# GPS_Schematic_Rev2_2.net
KiCad netlist of a schematic drawn in Altium Designer
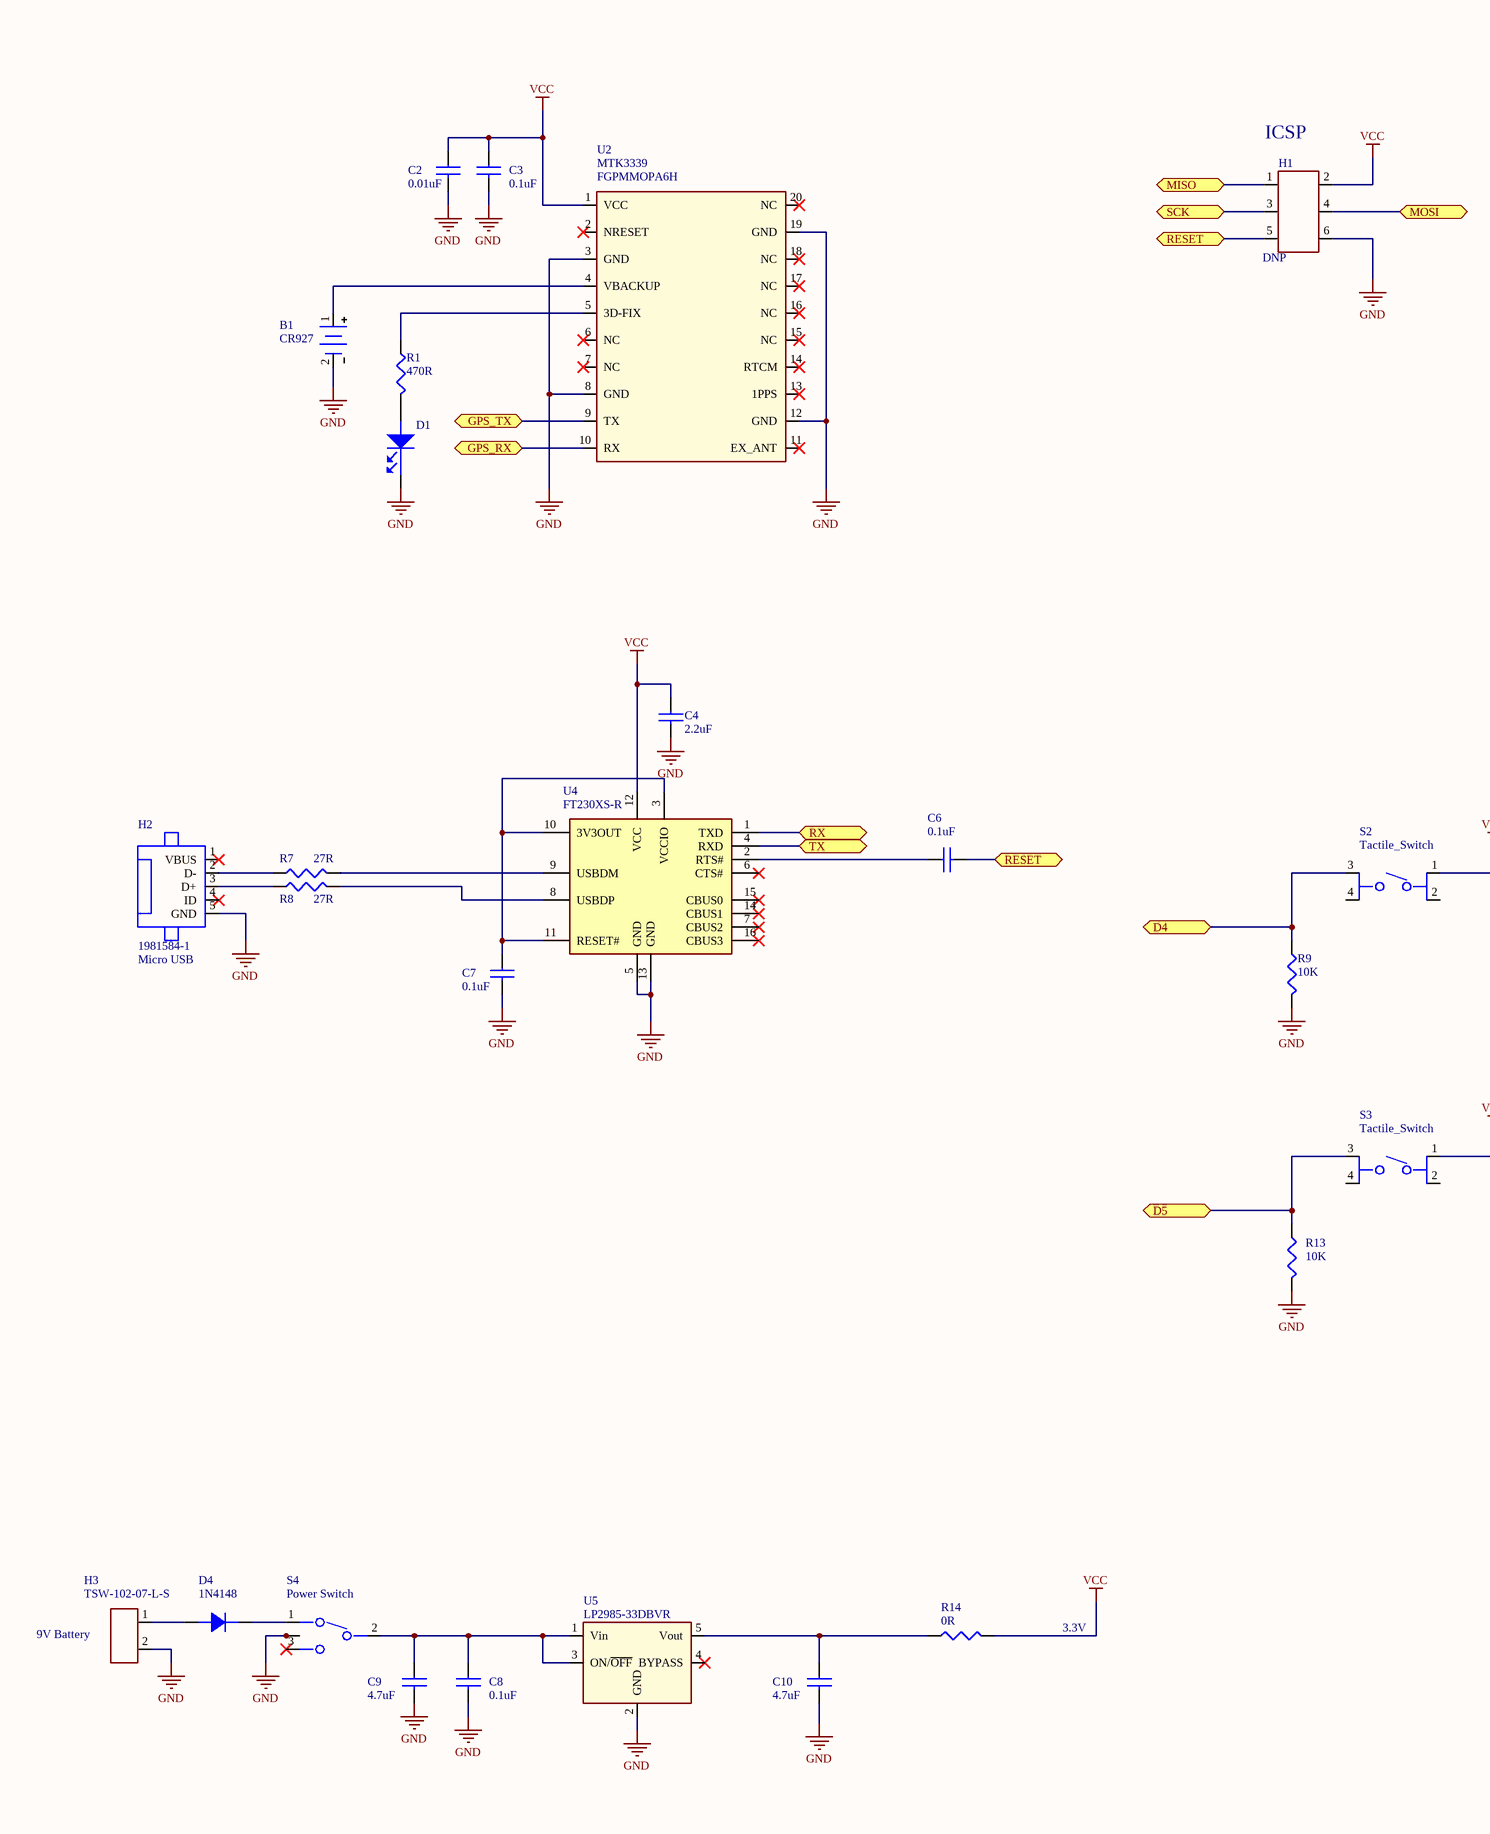
[diagram p0: GPS_Schematic_Rev2.2.SchDoc, left]
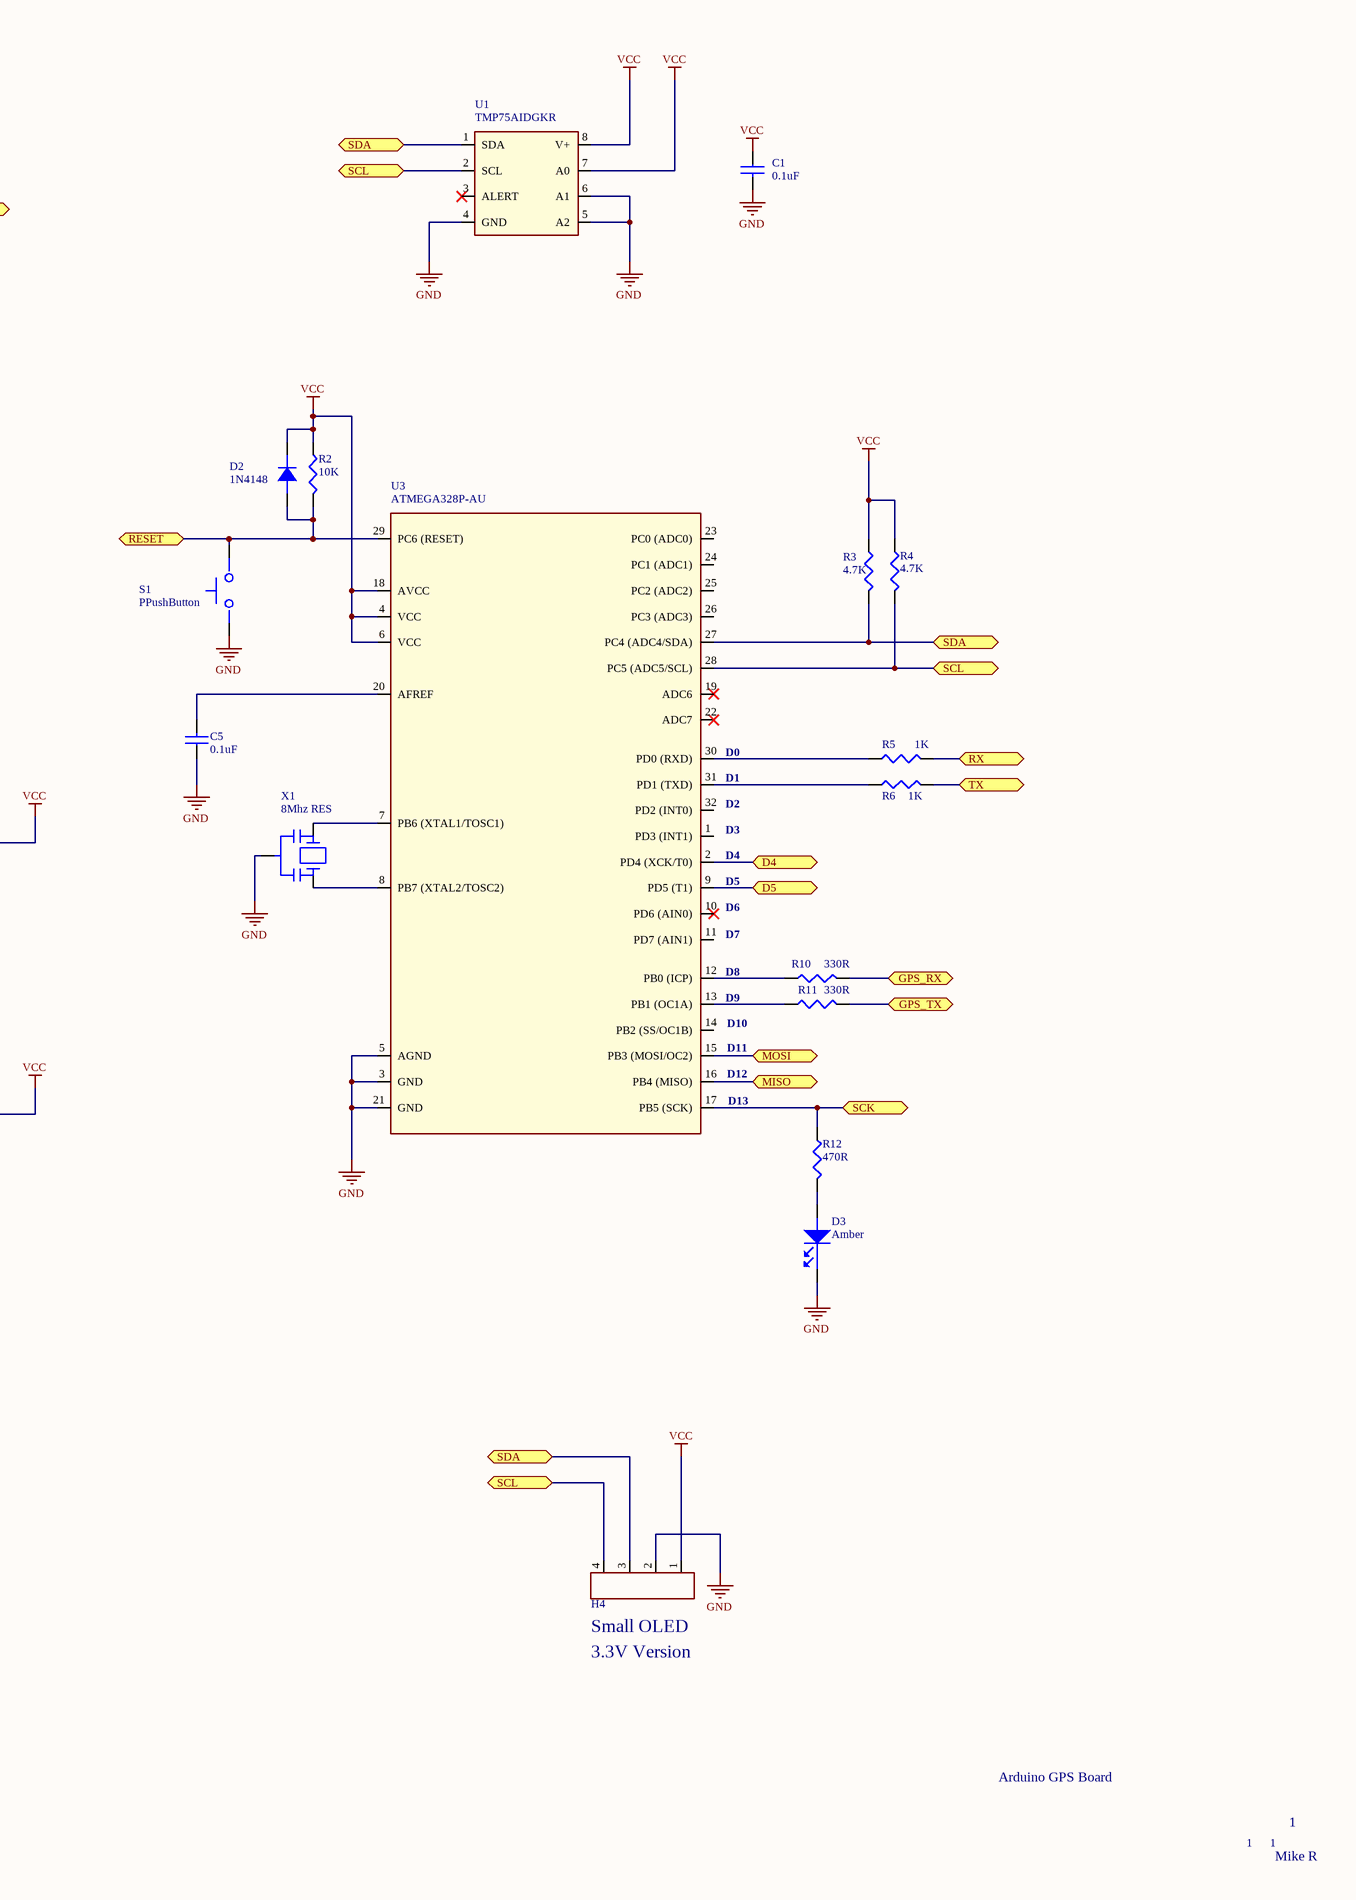
[diagram p1: GPS_Schematic_Rev2.2.SchDoc, right]

(export (version "E")
  (design (tool "Eeschema 10.0.6"))
  (components
    (comp (ref "B1")
      (value "CR927")
      (footprint "CR927 Mount")
      (description "Custom CR927 mount")
      (fields (field (name "PARTNUMBER") "202984"))
      (libsource (lib "Parts_Library") (part "CR927"))
    )
    (comp (ref "C1")
      (value "0.1uF")
      (footprint "CAPC1608X09L")
      (description "CAP CER 0.1uF, 0603")
      (libsource (lib "Parts_Library") (part "CAP_0603"))
    )
    (comp (ref "C2")
      (value "0.01uF")
      (footprint "CAPC1608X09L")
      (description "CAP CER 0.01uF, 0603")
      (libsource (lib "Parts_Library") (part "CAP_0603"))
    )
    (comp (ref "C3")
      (value "0.1uF")
      (footprint "CAPC1608X09L")
      (description "CAP CER 0.1uF, 0603")
      (libsource (lib "Parts_Library") (part "CAP_0603"))
    )
    (comp (ref "C4")
      (value "2.2uF")
      (footprint "CAPC1608X09L")
      (description "2.2uF, 0602")
      (libsource (lib "MAR") (part "CAP_0805"))
    )
    (comp (ref "C5")
      (value "0.1uF")
      (footprint "CAPC1608X09L")
      (description "CAP CER 0.1uF, 0603")
      (libsource (lib "Parts_Library") (part "CAP_0603"))
    )
    (comp (ref "C6")
      (value "0.1uF")
      (footprint "CAPC1608X09L")
      (description "CAP CER 0.1uF, 0603")
      (libsource (lib "Parts_Library") (part "CAP_0603"))
    )
    (comp (ref "C7")
      (value "0.1uF")
      (footprint "CAPC1608X09L")
      (description "CAP CER 0.1uF, 0603")
      (libsource (lib "Parts_Library") (part "CAP_0603"))
    )
    (comp (ref "C8")
      (value "0.1uF")
      (footprint "CAPC1608X09L")
      (description "CAP CER 0.1uF, 0603")
      (libsource (lib "Parts_Library") (part "CAP_0603"))
    )
    (comp (ref "C9")
      (value "4.7uF")
      (footprint "CAPC3216X160L")
      (description "CAP CER 4.7uF, 1206")
      (fields (field (name "Comment") "CAP_1206"))
      (libsource (lib "Parts_Library") (part "CAP_1206"))
    )
    (comp (ref "C10")
      (value "4.7uF")
      (footprint "CAPC3216X160L")
      (description "CAP CER 4.7uF, 1206")
      (fields (field (name "Comment") "CAP_1206"))
      (libsource (lib "Parts_Library") (part "CAP_1206"))
    )
    (comp (ref "D1")
      (value "Green LED")
      (footprint "LED1608X55N-GREEN")
      (description "LED_0603")
      (libsource (lib "Parts_Library") (part "LED_0603"))
    )
    (comp (ref "D2")
      (value "1N4148")
      (footprint "SOD123")
      (description "DIODE SWITCH 100V 0.15A SOD123")
      (fields (field (name "MANUFACTURER") "Micro Commercial") (field (name "PARTNUMBER") "1N4148W-TP"))
      (libsource (lib "MAR") (part "1N4148W-TP"))
    )
    (comp (ref "D3")
      (value "LED_0603")
      (footprint "LED1608X55N-YELLOW")
      (fields (field (name "PARTNUMBER") "Amber"))
      (libsource (lib "MAR") (part "LED_0603"))
    )
    (comp (ref "D4")
      (value "1N4148")
      (footprint "SOD123")
      (description "DIODE SWITCH 100V 0.15A SOD123")
      (fields (field (name "MANUFACTURER") "Micro Commercial") (field (name "PARTNUMBER") "1N4148W-TP"))
      (libsource (lib "MAR") (part "1N4148W-TP"))
    )
    (comp (ref "H1")
      (value "DNP")
      (footprint "HDR3X2")
      (description "CONN HEADER 3X2POS .100\" PADS")
      (libsource (lib "Parts_Library") (part "CON3X2"))
    )
    (comp (ref "H2")
      (value "Micro USB")
      (footprint "1981584-1")
      (description "CONN RCPT MICRO USB TYPE AB")
      (fields (field (name "MANUFACTURER") "TE Connectivity") (field (name "PARTNUMBER") "1981584-1"))
      (libsource (lib "MAR") (part "1981584-1"))
    )
    (comp (ref "H3")
      (value "TSW-102-07-L-S")
      (footprint "HDR1X2")
      (description "CONN HEADER 2POS .100\" SGL GOLD")
      (fields (field (name "MANUFACTURER") "Samtec"))
      (libsource (lib "Parts_Library") (part "TSW-102-07-L-S"))
    )
    (comp (ref "H4")
      (value "TSW-104-07-L-S")
      (footprint "HDR1X4-Empty")
      (description "CONN HEADER 4POS .100\" SGL GOLD")
      (fields (field (name "MANUFACTURER") "Samtec"))
      (libsource (lib "Parts_Library") (part "TSW-104-07-L-S"))
    )
    (comp (ref "R1")
      (value "470R")
      (footprint "RESC1608X06L")
      (description "RES 0603")
      (libsource (lib "MAR") (part "RES_0603"))
    )
    (comp (ref "R2")
      (value "10K")
      (footprint "RESC1608X06L")
      (description "RES 0603")
      (libsource (lib "MAR") (part "RES_0603"))
    )
    (comp (ref "R3")
      (value "4.7K")
      (footprint "RESC1608X06L")
      (description "RES 0603")
      (libsource (lib "MAR") (part "RES_0603"))
    )
    (comp (ref "R4")
      (value "4.7K")
      (footprint "RESC1608X06L")
      (description "RES 0603")
      (libsource (lib "MAR") (part "RES_0603"))
    )
    (comp (ref "R5")
      (value "1K")
      (footprint "RESC1608X06L")
      (description "RES 0603")
      (libsource (lib "MAR") (part "RES_0603"))
    )
    (comp (ref "R6")
      (value "1K")
      (footprint "RESC1608X06L")
      (description "RES 0603")
      (libsource (lib "MAR") (part "RES_0603"))
    )
    (comp (ref "R7")
      (value "27R")
      (footprint "RESC1608X06L")
      (description "RES 0603")
      (libsource (lib "MAR") (part "RES_0603"))
    )
    (comp (ref "R8")
      (value "27R")
      (footprint "RESC1608X06L")
      (description "RES 0603")
      (libsource (lib "MAR") (part "RES_0603"))
    )
    (comp (ref "R9")
      (value "10K")
      (footprint "RESC1608X06L")
      (description "RES 0603")
      (libsource (lib "MAR") (part "RES_0603"))
    )
    (comp (ref "R10")
      (value "330R")
      (footprint "RESC1608X06L")
      (description "RES 0603")
      (libsource (lib "MAR") (part "RES_0603"))
    )
    (comp (ref "R11")
      (value "330R")
      (footprint "RESC1608X06L")
      (description "RES 0603")
      (libsource (lib "MAR") (part "RES_0603"))
    )
    (comp (ref "R12")
      (value "470R")
      (footprint "RESC1608X06L")
      (description "RES 0603")
      (libsource (lib "MAR") (part "RES_0603"))
    )
    (comp (ref "R13")
      (value "10K")
      (footprint "RESC1608X06L")
      (description "RES 0603")
      (libsource (lib "MAR") (part "RES_0603"))
    )
    (comp (ref "R14")
      (value "0R")
      (footprint "RESC1608X06L")
      (description "RES 0603")
      (libsource (lib "MAR") (part "RES_0603"))
    )
    (comp (ref "S1")
      (value "PPushButton")
      (footprint "TL1015AF160QG")
      (description "DX_SWITCH TACTILE")
      (fields (field (name "PARTNUMBER") "122514"))
      (libsource (lib "MAR") (part "DX_MINI_TACT_SWITCH"))
    )
    (comp (ref "S2")
      (value "Tactile_Switch")
      (footprint "FSM6JSMA")
      (description "SWITCH TACTILE SPST-NO 0.05A 12V")
      (fields (field (name "MANUFACTURER") "TE Connectivity") (field (name "PARTNUMBER") "FSM6JSMA"))
      (libsource (lib "Parts_Library") (part "FSM6JSMA"))
    )
    (comp (ref "S3")
      (value "Tactile_Switch")
      (footprint "FSM6JSMA")
      (description "SWITCH TACTILE SPST-NO 0.05A 12V")
      (fields (field (name "MANUFACTURER") "TE Connectivity") (field (name "PARTNUMBER") "FSM6JSMA"))
      (libsource (lib "Parts_Library") (part "FSM6JSMA"))
    )
    (comp (ref "S4")
      (value "~")
      (footprint "SLIDE_SWITCH_DX")
      (description "DX_SWITCH SLIDE SPDT R/A")
      (fields (field (name "PARTNUMBER") "122531"))
      (libsource (lib "MAR") (part "DX_SLIDE_SWITCH"))
    )
    (comp (ref "U1")
      (value "TMP75AIDGKR")
      (footprint "MSOP-8N - NOPAD")
      (description "IC DGTL TEMP SENSOR 2WIRE 8-MSOP")
      (fields (field (name "MANUFACTURER") "Maxim") (field (name "PARTNUMBER") "TMP75AIDGKR"))
      (libsource (lib "MAR") (part "TMP75AIDGKR"))
    )
    (comp (ref "U2")
      (value "MTK3339")
      (footprint "FGPMMOPA6H")
      (description "GPS Chip - FGPMMOPA6H")
      (fields (field (name "MANUFACTURER") "Global Top") (field (name "PARTNUMBER") "FGPMMOPA6H"))
      (libsource (lib "MAR") (part "MTK3339"))
    )
    (comp (ref "U3")
      (value "ATMEGA328P-AU")
      (footprint "TQFP80P700X700-32N")
      (description "MCU AVR 32K FLASH 32TQFP")
      (fields (field (name "MANUFACTURER") "Atmel") (field (name "PARTNUMBER") "ATMEGA328P-AU"))
      (libsource (lib "MAR") (part "ATMEGA328P-AU"))
    )
    (comp (ref "U4")
      (value "FT230XS-R")
      (footprint "SOP65P602X173-16N")
      (description "IC USB SERIAL BASIC UART 16SSOP")
      (fields (field (name "MANUFACTURER") "FTDI") (field (name "PARTNUMBER") "FT230XS-R"))
      (libsource (lib "MAR") (part "FT230XS-R"))
    )
    (comp (ref "U5")
      (value "LP2985-33DBVR")
      (footprint "SOT95P280X144-5N")
      (description "IC REG LDO 3.3V .15A SOT23-5")
      (fields (field (name "MANUFACTURER") "Texas Instruments") (field (name "PARTNUMBER") "LP2985-33DBVR"))
      (libsource (lib "MAR") (part "LP2985-33DBVR"))
    )
    (comp (ref "X1")
      (value "8Mhz RES")
      (footprint "CSTCE")
      (description "CER RESONATOR 8.0MHZ SMD")
      (fields (field (name "PARTNUMBER") "CSTCE8M00G55-R0") (field (name "MANUFACTURER") "Murata"))
      (libsource (lib "Parts_Library") (part "CSTCE8M00G55-R0"))
    )
  )
  (nets
    (net (code "1") (name "/D4") (class "Default")
      (node (ref "R9") (pin "1") (pinfunction "1_1") (pintype "passive"))
      (node (ref "S2") (pin "3") (pintype "passive"))
      (node (ref "U3") (pin "2") (pinfunction "PD4_(XCK/T0)_2") (pintype "passive"))
    )
    (net (code "2") (name "/D5") (class "Default")
      (node (ref "R13") (pin "1") (pinfunction "1_1") (pintype "passive"))
      (node (ref "S3") (pin "3") (pintype "passive"))
      (node (ref "U3") (pin "9") (pinfunction "PD5_(T1)_9") (pintype "passive"))
    )
    (net (code "3") (name "/GPS_RX") (class "Default")
      (node (ref "R10") (pin "2") (pinfunction "2_2") (pintype "passive"))
      (node (ref "U2") (pin "10") (pinfunction "RX_10") (pintype "passive"))
    )
    (net (code "4") (name "/GPS_TX") (class "Default")
      (node (ref "R11") (pin "2") (pinfunction "2_2") (pintype "passive"))
      (node (ref "U2") (pin "9") (pinfunction "TX_9") (pintype "passive"))
    )
    (net (code "5") (name "/MISO") (class "Default")
      (node (ref "H1") (pin "1") (pintype "passive"))
      (node (ref "U3") (pin "16") (pinfunction "PB4_(MISO)_16") (pintype "passive"))
    )
    (net (code "6") (name "/MOSI") (class "Default")
      (node (ref "H1") (pin "4") (pintype "passive"))
      (node (ref "U3") (pin "15") (pinfunction "PB3_(MOSI/OC2)_15") (pintype "passive"))
    )
    (net (code "7") (name "/RESET") (class "Default")
      (node (ref "C6") (pin "2") (pinfunction "2_2") (pintype "passive"))
      (node (ref "D2") (pin "2") (pinfunction "Annode_2") (pintype "passive"))
      (node (ref "H1") (pin "5") (pintype "passive"))
      (node (ref "R2") (pin "2") (pinfunction "2_2") (pintype "passive"))
      (node (ref "S1") (pin "2") (pinfunction "B_2") (pintype "passive"))
      (node (ref "U3") (pin "29") (pinfunction "PC6_(RESET)_29") (pintype "passive"))
    )
    (net (code "8") (name "/RX") (class "Default")
      (node (ref "R5") (pin "2") (pinfunction "2_2") (pintype "passive"))
      (node (ref "U4") (pin "1") (pinfunction "TXD_1") (pintype "passive"))
    )
    (net (code "9") (name "/SCK") (class "Default")
      (node (ref "H1") (pin "3") (pintype "passive"))
      (node (ref "R12") (pin "1") (pinfunction "1_1") (pintype "passive"))
      (node (ref "U3") (pin "17") (pinfunction "PB5_(SCK)_17") (pintype "passive"))
    )
    (net (code "10") (name "/SCL") (class "Default")
      (node (ref "H4") (pin "4") (pintype "passive"))
      (node (ref "R4") (pin "2") (pinfunction "2_2") (pintype "passive"))
      (node (ref "U1") (pin "2") (pinfunction "SCL_2") (pintype "passive"))
      (node (ref "U3") (pin "28") (pinfunction "PC5_(ADC5/SCL)_28") (pintype "passive"))
    )
    (net (code "11") (name "/SDA") (class "Default")
      (node (ref "H4") (pin "3") (pintype "passive"))
      (node (ref "R3") (pin "2") (pinfunction "2_2") (pintype "passive"))
      (node (ref "U1") (pin "1") (pinfunction "SDA_1") (pintype "passive"))
      (node (ref "U3") (pin "27") (pinfunction "PC4_(ADC4/SDA)_27") (pintype "passive"))
    )
    (net (code "12") (name "/TX") (class "Default")
      (node (ref "R6") (pin "2") (pinfunction "2_2") (pintype "passive"))
      (node (ref "U4") (pin "4") (pinfunction "RXD_4") (pintype "passive"))
    )
    (net (code "13") (name "GND") (class "Default")
      (node (ref "B1") (pin "2") (pinfunction "-_2") (pintype "passive"))
      (node (ref "C1") (pin "2") (pinfunction "2_2") (pintype "passive"))
      (node (ref "C10") (pin "2") (pinfunction "2_2") (pintype "passive"))
      (node (ref "C2") (pin "2") (pinfunction "2_2") (pintype "passive"))
      (node (ref "C3") (pin "2") (pinfunction "2_2") (pintype "passive"))
      (node (ref "C4") (pin "2") (pinfunction "2_2") (pintype "passive"))
      (node (ref "C5") (pin "1") (pinfunction "1_1") (pintype "passive"))
      (node (ref "C7") (pin "2") (pinfunction "2_2") (pintype "passive"))
      (node (ref "C8") (pin "2") (pinfunction "2_2") (pintype "passive"))
      (node (ref "C9") (pin "2") (pinfunction "2_2") (pintype "passive"))
      (node (ref "D1") (pin "1") (pinfunction "CATHODE_1") (pintype "passive"))
      (node (ref "D3") (pin "1") (pinfunction "CATHODE_1") (pintype "passive"))
      (node (ref "H1") (pin "6") (pintype "passive"))
      (node (ref "H2") (pin "5") (pinfunction "GND_5") (pintype "power_in"))
      (node (ref "H3") (pin "2") (pintype "passive"))
      (node (ref "H4") (pin "2") (pintype "passive"))
      (node (ref "R13") (pin "2") (pinfunction "2_2") (pintype "passive"))
      (node (ref "R9") (pin "2") (pinfunction "2_2") (pintype "passive"))
      (node (ref "S1") (pin "1") (pinfunction "A_1") (pintype "passive"))
      (node (ref "S4") (pin "4") (pinfunction "GND_4") (pintype "passive"))
      (node (ref "S4") (pin "5") (pinfunction "GND_5") (pintype "passive"))
      (node (ref "U1") (pin "4") (pinfunction "GND_4") (pintype "power_in"))
      (node (ref "U1") (pin "5") (pinfunction "A2_5") (pintype "passive"))
      (node (ref "U1") (pin "6") (pinfunction "A1_6") (pintype "passive"))
      (node (ref "U2") (pin "12") (pinfunction "GND_12") (pintype "power_in"))
      (node (ref "U2") (pin "19") (pinfunction "GND_19") (pintype "power_in"))
      (node (ref "U2") (pin "3") (pinfunction "GND_3") (pintype "power_in"))
      (node (ref "U2") (pin "8") (pinfunction "GND_8") (pintype "power_in"))
      (node (ref "U3") (pin "21") (pinfunction "GND_21") (pintype "power_in"))
      (node (ref "U3") (pin "3") (pinfunction "GND_3") (pintype "power_in"))
      (node (ref "U3") (pin "5") (pinfunction "AGND_5") (pintype "power_in"))
      (node (ref "U4") (pin "13") (pinfunction "GND_13") (pintype "power_in"))
      (node (ref "U4") (pin "5") (pinfunction "GND_5") (pintype "power_in"))
      (node (ref "U5") (pin "2") (pinfunction "GND_2") (pintype "power_in"))
      (node (ref "X1") (pin "2") (pinfunction "2_2") (pintype "passive"))
    )
    (net (code "14") (name "Net-(B1-+)") (class "Default")
      (node (ref "B1") (pin "1") (pinfunction "+_1") (pintype "passive"))
      (node (ref "U2") (pin "4") (pinfunction "VBACKUP_4") (pintype "passive"))
    )
    (net (code "15") (name "Net-(D1-ANODE)") (class "Default")
      (node (ref "D1") (pin "2") (pinfunction "ANODE_2") (pintype "passive"))
      (node (ref "R1") (pin "2") (pinfunction "2_2") (pintype "passive"))
    )
    (net (code "16") (name "Net-(D3-ANODE)") (class "Default")
      (node (ref "D3") (pin "2") (pinfunction "ANODE_2") (pintype "passive"))
      (node (ref "R12") (pin "2") (pinfunction "2_2") (pintype "passive"))
    )
    (net (code "17") (name "Net-(D4-Annode)") (class "Default")
      (node (ref "D4") (pin "2") (pinfunction "Annode_2") (pintype "passive"))
      (node (ref "H3") (pin "1") (pintype "passive"))
    )
    (net (code "18") (name "Net-(D4-Cathode)") (class "Default")
      (node (ref "D4") (pin "1") (pinfunction "Cathode_1") (pintype "passive"))
      (node (ref "S4") (pin "1") (pinfunction "A_1") (pintype "passive"))
    )
    (net (code "19") (name "Net-(H2-D+)") (class "Default")
      (node (ref "H2") (pin "3") (pinfunction "D+_3") (pintype "passive"))
      (node (ref "R8") (pin "1") (pinfunction "1_1") (pintype "passive"))
    )
    (net (code "20") (name "Net-(H2-D-)") (class "Default")
      (node (ref "H2") (pin "2") (pinfunction "D-_2") (pintype "passive"))
      (node (ref "R7") (pin "1") (pinfunction "1_1") (pintype "passive"))
    )
    (net (code "21") (name "Net-(S4-Middle)") (class "Default")
      (node (ref "C8") (pin "1") (pinfunction "1_1") (pintype "passive"))
      (node (ref "C9") (pin "1") (pinfunction "1_1") (pintype "passive"))
      (node (ref "S4") (pin "2") (pinfunction "Middle_2") (pintype "passive"))
      (node (ref "U5") (pin "1") (pinfunction "Vin_1") (pintype "passive"))
      (node (ref "U5") (pin "3") (pinfunction "ON/~{OFF}_3") (pintype "passive"))
    )
    (net (code "22") (name "Net-(U2-3D-FIX)") (class "Default")
      (node (ref "R1") (pin "1") (pinfunction "1_1") (pintype "passive"))
      (node (ref "U2") (pin "5") (pinfunction "3D-FIX_5") (pintype "passive"))
    )
    (net (code "23") (name "Net-(U3-AFREF)") (class "Default")
      (node (ref "C5") (pin "2") (pinfunction "2_2") (pintype "passive"))
      (node (ref "U3") (pin "20") (pinfunction "AFREF_20") (pintype "passive"))
    )
    (net (code "24") (name "Net-(U3-PB0_(ICP))") (class "Default")
      (node (ref "R10") (pin "1") (pinfunction "1_1") (pintype "passive"))
      (node (ref "U3") (pin "12") (pinfunction "PB0_(ICP)_12") (pintype "passive"))
    )
    (net (code "25") (name "Net-(U3-PB1_(OC1A))") (class "Default")
      (node (ref "R11") (pin "1") (pinfunction "1_1") (pintype "passive"))
      (node (ref "U3") (pin "13") (pinfunction "PB1_(OC1A)_13") (pintype "passive"))
    )
    (net (code "26") (name "Net-(U3-PB6_(XTAL1{slash}TOSC1))") (class "Default")
      (node (ref "U3") (pin "7") (pinfunction "PB6_(XTAL1/TOSC1)_7") (pintype "passive"))
      (node (ref "X1") (pin "1") (pinfunction "1_1") (pintype "passive"))
    )
    (net (code "27") (name "Net-(U3-PB7_(XTAL2{slash}TOSC2))") (class "Default")
      (node (ref "U3") (pin "8") (pinfunction "PB7_(XTAL2/TOSC2)_8") (pintype "passive"))
      (node (ref "X1") (pin "3") (pinfunction "3_3") (pintype "passive"))
    )
    (net (code "28") (name "Net-(U3-PD0_(RXD))") (class "Default")
      (node (ref "R5") (pin "1") (pinfunction "1_1") (pintype "passive"))
      (node (ref "U3") (pin "30") (pinfunction "PD0_(RXD)_30") (pintype "passive"))
    )
    (net (code "29") (name "Net-(U3-PD1_(TXD))") (class "Default")
      (node (ref "R6") (pin "1") (pinfunction "1_1") (pintype "passive"))
      (node (ref "U3") (pin "31") (pinfunction "PD1_(TXD)_31") (pintype "passive"))
    )
    (net (code "30") (name "Net-(U4-3V3OUT)") (class "Default")
      (node (ref "C7") (pin "1") (pinfunction "1_1") (pintype "passive"))
      (node (ref "U4") (pin "10") (pinfunction "3V3OUT_10") (pintype "passive"))
      (node (ref "U4") (pin "11") (pinfunction "RESET#_11") (pintype "passive"))
      (node (ref "U4") (pin "3") (pinfunction "VCCIO_3") (pintype "passive"))
    )
    (net (code "31") (name "Net-(U4-RTS#)") (class "Default")
      (node (ref "C6") (pin "1") (pinfunction "1_1") (pintype "passive"))
      (node (ref "U4") (pin "2") (pinfunction "RTS#_2") (pintype "passive"))
    )
    (net (code "32") (name "Net-(U4-USBDM)") (class "Default")
      (node (ref "R7") (pin "2") (pinfunction "2_2") (pintype "passive"))
      (node (ref "U4") (pin "9") (pinfunction "USBDM_9") (pintype "passive"))
    )
    (net (code "33") (name "Net-(U4-USBDP)") (class "Default")
      (node (ref "R8") (pin "2") (pinfunction "2_2") (pintype "passive"))
      (node (ref "U4") (pin "8") (pinfunction "USBDP_8") (pintype "passive"))
    )
    (net (code "34") (name "Net-(U5-Vout)") (class "Default")
      (node (ref "C10") (pin "1") (pinfunction "1_1") (pintype "passive"))
      (node (ref "R14") (pin "1") (pinfunction "1_1") (pintype "passive"))
      (node (ref "U5") (pin "5") (pinfunction "Vout_5") (pintype "passive"))
    )
    (net (code "35") (name "VCC") (class "Default")
      (node (ref "C1") (pin "1") (pinfunction "1_1") (pintype "passive"))
      (node (ref "C2") (pin "1") (pinfunction "1_1") (pintype "passive"))
      (node (ref "C3") (pin "1") (pinfunction "1_1") (pintype "passive"))
      (node (ref "C4") (pin "1") (pinfunction "1_1") (pintype "passive"))
      (node (ref "D2") (pin "1") (pinfunction "Cathode_1") (pintype "passive"))
      (node (ref "H1") (pin "2") (pintype "passive"))
      (node (ref "H4") (pin "1") (pintype "passive"))
      (node (ref "R14") (pin "2") (pinfunction "2_2") (pintype "passive"))
      (node (ref "R2") (pin "1") (pinfunction "1_1") (pintype "passive"))
      (node (ref "R3") (pin "1") (pinfunction "1_1") (pintype "passive"))
      (node (ref "R4") (pin "1") (pinfunction "1_1") (pintype "passive"))
      (node (ref "S2") (pin "1") (pintype "passive"))
      (node (ref "S3") (pin "1") (pintype "passive"))
      (node (ref "U1") (pin "7") (pinfunction "A0_7") (pintype "passive"))
      (node (ref "U1") (pin "8") (pinfunction "V+_8") (pintype "power_in"))
      (node (ref "U2") (pin "1") (pinfunction "VCC_1") (pintype "power_in"))
      (node (ref "U3") (pin "18") (pinfunction "AVCC_18") (pintype "power_in"))
      (node (ref "U3") (pin "4") (pinfunction "VCC_4") (pintype "power_in"))
      (node (ref "U3") (pin "6") (pinfunction "VCC_6") (pintype "power_in"))
      (node (ref "U4") (pin "12") (pinfunction "VCC_12") (pintype "power_in"))
    )
    (net (code "36") (name "unconnected-(H2-ID-Pad4)") (class "Default")
      (node (ref "H2") (pin "4") (pinfunction "ID_4") (pintype "passive+no_connect"))
    )
    (net (code "37") (name "unconnected-(H2-VBUS-Pad1)") (class "Default")
      (node (ref "H2") (pin "1") (pinfunction "VBUS_1") (pintype "power_in+no_connect"))
    )
    (net (code "38") (name "unconnected-(S2-Pad2)") (class "Default")
      (node (ref "S2") (pin "2") (pintype "passive"))
    )
    (net (code "39") (name "unconnected-(S2-Pad4)") (class "Default")
      (node (ref "S2") (pin "4") (pintype "passive"))
    )
    (net (code "40") (name "unconnected-(S3-Pad2)") (class "Default")
      (node (ref "S3") (pin "2") (pintype "passive"))
    )
    (net (code "41") (name "unconnected-(S3-Pad4)") (class "Default")
      (node (ref "S3") (pin "4") (pintype "passive"))
    )
    (net (code "42") (name "unconnected-(S4-B-Pad3)") (class "Default")
      (node (ref "S4") (pin "3") (pinfunction "B_3") (pintype "passive+no_connect"))
    )
    (net (code "43") (name "unconnected-(U1-ALERT-Pad3)") (class "Default")
      (node (ref "U1") (pin "3") (pinfunction "ALERT_3") (pintype "passive+no_connect"))
    )
    (net (code "44") (name "unconnected-(U2-1PPS-Pad13)") (class "Default")
      (node (ref "U2") (pin "13") (pinfunction "1PPS_13") (pintype "passive+no_connect"))
    )
    (net (code "45") (name "unconnected-(U2-EX_ANT-Pad11)") (class "Default")
      (node (ref "U2") (pin "11") (pinfunction "EX_ANT_11") (pintype "passive+no_connect"))
    )
    (net (code "46") (name "unconnected-(U2-NC-Pad6)") (class "Default")
      (node (ref "U2") (pin "6") (pinfunction "NC_6") (pintype "passive+no_connect"))
    )
    (net (code "47") (name "unconnected-(U2-NC-Pad7)") (class "Default")
      (node (ref "U2") (pin "7") (pinfunction "NC_7") (pintype "passive+no_connect"))
    )
    (net (code "48") (name "unconnected-(U2-NC-Pad15)") (class "Default")
      (node (ref "U2") (pin "15") (pinfunction "NC_15") (pintype "passive+no_connect"))
    )
    (net (code "49") (name "unconnected-(U2-NC-Pad16)") (class "Default")
      (node (ref "U2") (pin "16") (pinfunction "NC_16") (pintype "passive+no_connect"))
    )
    (net (code "50") (name "unconnected-(U2-NC-Pad17)") (class "Default")
      (node (ref "U2") (pin "17") (pinfunction "NC_17") (pintype "passive+no_connect"))
    )
    (net (code "51") (name "unconnected-(U2-NC-Pad18)") (class "Default")
      (node (ref "U2") (pin "18") (pinfunction "NC_18") (pintype "passive+no_connect"))
    )
    (net (code "52") (name "unconnected-(U2-NC-Pad20)") (class "Default")
      (node (ref "U2") (pin "20") (pinfunction "NC_20") (pintype "passive+no_connect"))
    )
    (net (code "53") (name "unconnected-(U2-NRESET-Pad2)") (class "Default")
      (node (ref "U2") (pin "2") (pinfunction "NRESET_2") (pintype "passive+no_connect"))
    )
    (net (code "54") (name "unconnected-(U2-RTCM-Pad14)") (class "Default")
      (node (ref "U2") (pin "14") (pinfunction "RTCM_14") (pintype "passive+no_connect"))
    )
    (net (code "55") (name "unconnected-(U3-ADC6-Pad19)") (class "Default")
      (node (ref "U3") (pin "19") (pinfunction "ADC6_19") (pintype "passive+no_connect"))
    )
    (net (code "56") (name "unconnected-(U3-ADC7-Pad22)") (class "Default")
      (node (ref "U3") (pin "22") (pinfunction "ADC7_22") (pintype "passive+no_connect"))
    )
    (net (code "57") (name "unconnected-(U3-PB2_(SS{slash}OC1B)-Pad14)") (class "Default")
      (node (ref "U3") (pin "14") (pinfunction "PB2_(SS/OC1B)_14") (pintype "passive"))
    )
    (net (code "58") (name "unconnected-(U3-PC0_(ADC0)-Pad23)") (class "Default")
      (node (ref "U3") (pin "23") (pinfunction "PC0_(ADC0)_23") (pintype "passive"))
    )
    (net (code "59") (name "unconnected-(U3-PC1_(ADC1)-Pad24)") (class "Default")
      (node (ref "U3") (pin "24") (pinfunction "PC1_(ADC1)_24") (pintype "passive"))
    )
    (net (code "60") (name "unconnected-(U3-PC2_(ADC2)-Pad25)") (class "Default")
      (node (ref "U3") (pin "25") (pinfunction "PC2_(ADC2)_25") (pintype "passive"))
    )
    (net (code "61") (name "unconnected-(U3-PC3_(ADC3)-Pad26)") (class "Default")
      (node (ref "U3") (pin "26") (pinfunction "PC3_(ADC3)_26") (pintype "passive"))
    )
    (net (code "62") (name "unconnected-(U3-PD2_(INT0)-Pad32)") (class "Default")
      (node (ref "U3") (pin "32") (pinfunction "PD2_(INT0)_32") (pintype "passive"))
    )
    (net (code "63") (name "unconnected-(U3-PD3_(INT1)-Pad1)") (class "Default")
      (node (ref "U3") (pin "1") (pinfunction "PD3_(INT1)_1") (pintype "passive"))
    )
    (net (code "64") (name "unconnected-(U3-PD6_(AIN0)-Pad10)") (class "Default")
      (node (ref "U3") (pin "10") (pinfunction "PD6_(AIN0)_10") (pintype "passive+no_connect"))
    )
    (net (code "65") (name "unconnected-(U3-PD7_(AIN1)-Pad11)") (class "Default")
      (node (ref "U3") (pin "11") (pinfunction "PD7_(AIN1)_11") (pintype "passive"))
    )
    (net (code "66") (name "unconnected-(U4-CBUS0-Pad15)") (class "Default")
      (node (ref "U4") (pin "15") (pinfunction "CBUS0_15") (pintype "passive+no_connect"))
    )
    (net (code "67") (name "unconnected-(U4-CBUS1-Pad14)") (class "Default")
      (node (ref "U4") (pin "14") (pinfunction "CBUS1_14") (pintype "passive+no_connect"))
    )
    (net (code "68") (name "unconnected-(U4-CBUS2-Pad7)") (class "Default")
      (node (ref "U4") (pin "7") (pinfunction "CBUS2_7") (pintype "passive+no_connect"))
    )
    (net (code "69") (name "unconnected-(U4-CBUS3-Pad16)") (class "Default")
      (node (ref "U4") (pin "16") (pinfunction "CBUS3_16") (pintype "passive+no_connect"))
    )
    (net (code "70") (name "unconnected-(U4-CTS#-Pad6)") (class "Default")
      (node (ref "U4") (pin "6") (pinfunction "CTS#_6") (pintype "passive+no_connect"))
    )
    (net (code "71") (name "unconnected-(U5-BYPASS-Pad4)") (class "Default")
      (node (ref "U5") (pin "4") (pinfunction "BYPASS_4") (pintype "passive+no_connect"))
    )
  )
)
